# Supply_Fast_Servo.net
KiCad netlist of a schematic drawn in Altium Designer
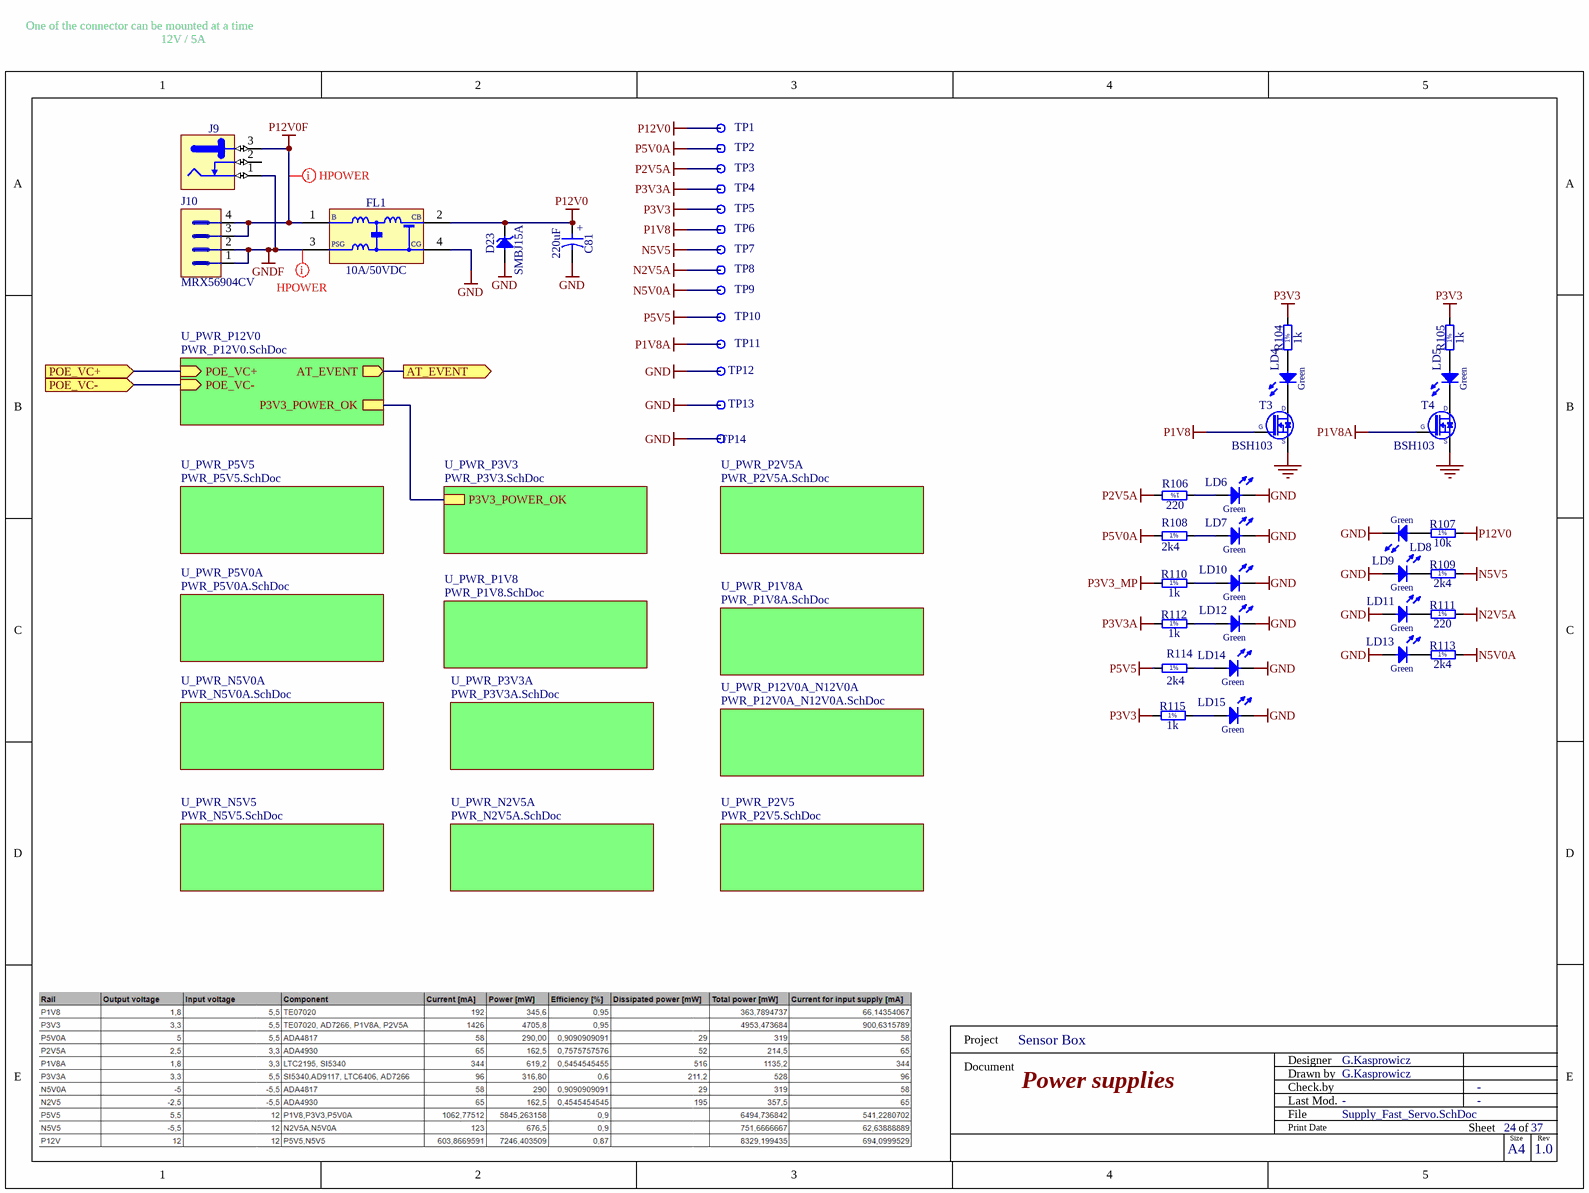
[diagram p0: Supply_Fast_Servo.SchDoc]

(export (version "E")
  (design (tool "Eeschema 10.0.6"))
  (components
    (comp (ref "C81")
      (value "220uF")
      (footprint "CAPAE830X620N")
      (description "Polarised capacitor")
      (fields
        (field (name "PART NUMBER") "CAE830-620_220UF_16V_20%")
        (field (name "VOLTAGE") "16V")
        (field (name "AUTHOR") "CERN DEM JLC")
      )
      (libsource (lib "Capacitors") (part "Capacitor - polarized"))
    )
    (comp (ref "D23")
      (value "SMBJ15A")
      (footprint "DIOM5336X265N")
      (description "Zener Diode")
      (fields
        (field (name "VOLTAGE") "15V")
        (field (name "POWER") "600W")
        (field (name "AUTHOR") "CERN DEM JLC")
      )
      (libsource (lib "ICs And Semiconductors") (part "Diode Zener"))
    )
    (comp (ref "FL1")
      (value "10A/50VDC")
      (footprint "FIL_MURATA_BNX02")
      (description "Block Type EMIFIL (LC Combined)")
      (fields
        (field (name "PART NUMBER") "FIL_MURATA_BNX022-01L")
        (field (name "MANUFACTURER") "MURATA")
        (field (name "AUTHOR") "CERN DEM JLC")
      )
      (libsource (lib "Inductors & Transformers") (part "FIL_MURATA_BNX02"))
    )
    (comp (ref "J9")
      (value "Jack")
      (footprint "SWITCHCRAFT_L712RA")
      (description "24V /3. 5A, 2.1mm Diameter Pin, SMD DC Power Supply Connector With  Break Contact")
      (fields
        (field (name "PART NUMBER") "SWITCHCRAFT_L712RA")
        (field (name "MANUFACTURER") "SWITCHCRAFT")
        (field (name "AUTHOR") "GK")
      )
      (libsource (lib "Stabilizer") (part "CON_DC_5A_THT_RA"))
    )
    (comp (ref "J10")
      (value "MRX56904CV")
      (footprint "MRX56904CV")
      (description "4.2mm cripm terminal header")
      (libsource (lib "Stabilizer") (part "CON_CRIMP_4.2mm_RA_4"))
    )
    (comp (ref "LD4")
      (value "Green")
      (footprint "LED_KINGBRIGHT_KPH-1608CGCK")
      (description "LED Green 1C 2A")
      (fields
        (field (name "MANUFACTURER PART NUMBER") "KPH-1608CGCK")
        (field (name "PART NUMBER") "LED_KINGBRIGHT_KPH-1608CGCK")
        (field (name "AUTHOR") "CERN DEM JLC")
      )
      (libsource (lib "ICs And Semiconductors") (part "LED Green 1C 2A"))
    )
    (comp (ref "LD5")
      (value "Green")
      (footprint "LED_KINGBRIGHT_KPH-1608CGCK")
      (description "LED Green 1C 2A")
      (fields
        (field (name "MANUFACTURER PART NUMBER") "KPH-1608CGCK")
        (field (name "PART NUMBER") "LED_KINGBRIGHT_KPH-1608CGCK")
        (field (name "AUTHOR") "CERN DEM JLC")
      )
      (libsource (lib "ICs And Semiconductors") (part "LED Green 1C 2A"))
    )
    (comp (ref "LD6")
      (value "Green")
      (footprint "LED_KINGBRIGHT_KPH-1608CGCK")
      (description "LED Green 1C 2A")
      (fields
        (field (name "PART NUMBER") "LED_KINGBRIGHT_KPH-1608CGCK")
        (field (name "MANUFACTURER") "KINGBRIGHT")
        (field (name "AUTHOR") "CERN DEM JLC")
      )
      (libsource (lib "ICs And Semiconductors") (part "LED Green 1C 2A"))
    )
    (comp (ref "LD7")
      (value "Green")
      (footprint "LED_KINGBRIGHT_KPH-1608CGCK")
      (description "LED Green 1C 2A")
      (fields
        (field (name "PART NUMBER") "LED_KINGBRIGHT_KPH-1608CGCK")
        (field (name "MANUFACTURER") "KINGBRIGHT")
        (field (name "AUTHOR") "CERN DEM JLC")
      )
      (libsource (lib "ICs And Semiconductors") (part "LED Green 1C 2A"))
    )
    (comp (ref "LD8")
      (value "Green")
      (footprint "LED_KINGBRIGHT_KPH-1608CGCK")
      (description "LED Green 1C 2A")
      (fields
        (field (name "PART NUMBER") "LED_KINGBRIGHT_KPH-1608CGCK")
        (field (name "MANUFACTURER") "KINGBRIGHT")
        (field (name "AUTHOR") "CERN DEM JLC")
      )
      (libsource (lib "ICs And Semiconductors") (part "LED Green 1C 2A"))
    )
    (comp (ref "LD9")
      (value "Green")
      (footprint "LED_KINGBRIGHT_KPH-1608CGCK")
      (description "LED Green 1C 2A")
      (fields
        (field (name "PART NUMBER") "LED_KINGBRIGHT_KPH-1608CGCK")
        (field (name "MANUFACTURER") "KINGBRIGHT")
        (field (name "AUTHOR") "CERN DEM JLC")
      )
      (libsource (lib "ICs And Semiconductors") (part "LED Green 1C 2A"))
    )
    (comp (ref "LD10")
      (value "Green")
      (footprint "LED_KINGBRIGHT_KPH-1608CGCK")
      (description "LED Green 1C 2A")
      (fields
        (field (name "PART NUMBER") "LED_KINGBRIGHT_KPH-1608CGCK")
        (field (name "MANUFACTURER") "KINGBRIGHT")
        (field (name "AUTHOR") "CERN DEM JLC")
      )
      (libsource (lib "ICs And Semiconductors") (part "LED Green 1C 2A"))
    )
    (comp (ref "LD11")
      (value "Green")
      (footprint "LED_KINGBRIGHT_KPH-1608CGCK")
      (description "LED Green 1C 2A")
      (fields
        (field (name "PART NUMBER") "LED_KINGBRIGHT_KPH-1608CGCK")
        (field (name "MANUFACTURER") "KINGBRIGHT")
        (field (name "AUTHOR") "CERN DEM JLC")
      )
      (libsource (lib "ICs And Semiconductors") (part "LED Green 1C 2A"))
    )
    (comp (ref "LD12")
      (value "Green")
      (footprint "LED_KINGBRIGHT_KPH-1608CGCK")
      (description "LED Green 1C 2A")
      (fields
        (field (name "PART NUMBER") "LED_KINGBRIGHT_KPH-1608CGCK")
        (field (name "MANUFACTURER") "KINGBRIGHT")
        (field (name "AUTHOR") "CERN DEM JLC")
      )
      (libsource (lib "ICs And Semiconductors") (part "LED Green 1C 2A"))
    )
    (comp (ref "LD13")
      (value "Green")
      (footprint "LED_KINGBRIGHT_KPH-1608CGCK")
      (description "LED Green 1C 2A")
      (fields
        (field (name "PART NUMBER") "LED_KINGBRIGHT_KPH-1608CGCK")
        (field (name "MANUFACTURER") "KINGBRIGHT")
        (field (name "AUTHOR") "CERN DEM JLC")
      )
      (libsource (lib "ICs And Semiconductors") (part "LED Green 1C 2A"))
    )
    (comp (ref "LD14")
      (value "Green")
      (footprint "LED_KINGBRIGHT_KPH-1608CGCK")
      (description "LED Green 1C 2A")
      (fields
        (field (name "PART NUMBER") "LED_KINGBRIGHT_KPH-1608CGCK")
        (field (name "MANUFACTURER") "KINGBRIGHT")
        (field (name "AUTHOR") "CERN DEM JLC")
      )
      (libsource (lib "ICs And Semiconductors") (part "LED Green 1C 2A"))
    )
    (comp (ref "LD15")
      (value "Green")
      (footprint "LED_KINGBRIGHT_KPH-1608CGCK")
      (description "LED Green 1C 2A")
      (fields
        (field (name "PART NUMBER") "LED_KINGBRIGHT_KPH-1608CGCK")
        (field (name "MANUFACTURER") "KINGBRIGHT")
        (field (name "AUTHOR") "CERN DEM JLC")
      )
      (libsource (lib "ICs And Semiconductors") (part "LED Green 1C 2A"))
    )
    (comp (ref "R104")
      (value "1k")
      (footprint "RESC1005X40N")
      (description "Resistor - 1%")
      (fields
        (field (name "PART NUMBER") "R0402_1K_1%_0.0625W_100PPM")
        (field (name "POWER") "0.0625W")
        (field (name "AUTHOR") "CERN DEM JLC")
      )
      (libsource (lib "Resistors") (part "Resistor - 1%"))
    )
    (comp (ref "R105")
      (value "1k")
      (footprint "RESC1005X40N")
      (description "Resistor - 1%")
      (fields
        (field (name "PART NUMBER") "R0402_1K_1%_0.0625W_100PPM")
        (field (name "POWER") "0.0625W")
        (field (name "AUTHOR") "CERN DEM JLC")
      )
      (libsource (lib "Resistors") (part "Resistor - 1%"))
    )
    (comp (ref "R106")
      (value "220")
      (footprint "RESC1608X55N")
      (description "Resistor - 1%")
      (fields
        (field (name "PART NUMBER") "R0603_220R_1%_0.1W_100PPM")
        (field (name "POWER") "0.1W")
        (field (name "AUTHOR") "CERN DEM JLC")
      )
      (libsource (lib "Resistors") (part "Resistor - 1%"))
    )
    (comp (ref "R107")
      (value "10k")
      (footprint "RESC1005X40N")
      (description "Resistor - 1%")
      (fields
        (field (name "PART NUMBER") "R0402_10K_1%_0.0625W_100PPM")
        (field (name "POWER") "0.0625W")
        (field (name "AUTHOR") "CERN DEM JLC")
      )
      (libsource (lib "Resistors") (part "Resistor - 1%"))
    )
    (comp (ref "R108")
      (value "2k4")
      (footprint "RESC1005X40N")
      (description "Resistor - 1%")
      (fields
        (field (name "PART NUMBER") "R0402_2K4_1%_0.0625W_100PPM")
        (field (name "POWER") "0.0625W")
        (field (name "AUTHOR") "CERN DEM JLC")
      )
      (libsource (lib "Resistors") (part "Resistor - 1%"))
    )
    (comp (ref "R109")
      (value "2k4")
      (footprint "RESC1005X40N")
      (description "Resistor - 1%")
      (fields
        (field (name "PART NUMBER") "R0402_2K4_1%_0.0625W_100PPM")
        (field (name "POWER") "0.0625W")
        (field (name "AUTHOR") "CERN DEM JLC")
      )
      (libsource (lib "Resistors") (part "Resistor - 1%"))
    )
    (comp (ref "R110")
      (value "1k")
      (footprint "RESC1005X40N")
      (description "Resistor - 1%")
      (fields
        (field (name "PART NUMBER") "R0402_1K_1%_0.0625W_100PPM")
        (field (name "POWER") "0.0625W")
        (field (name "AUTHOR") "CERN DEM JLC")
      )
      (libsource (lib "Resistors") (part "Resistor - 1%"))
    )
    (comp (ref "R111")
      (value "220")
      (footprint "RESC1608X55N")
      (description "Resistor - 1%")
      (fields
        (field (name "PART NUMBER") "R0603_220R_1%_0.1W_100PPM")
        (field (name "POWER") "0.1W")
        (field (name "AUTHOR") "CERN DEM JLC")
      )
      (libsource (lib "Resistors") (part "Resistor - 1%"))
    )
    (comp (ref "R112")
      (value "1k")
      (footprint "RESC1005X40N")
      (description "Resistor - 1%")
      (fields
        (field (name "PART NUMBER") "R0402_1K_1%_0.0625W_100PPM")
        (field (name "POWER") "0.0625W")
        (field (name "AUTHOR") "CERN DEM JLC")
      )
      (libsource (lib "Resistors") (part "Resistor - 1%"))
    )
    (comp (ref "R113")
      (value "2k4")
      (footprint "RESC1005X40N")
      (description "Resistor - 1%")
      (fields
        (field (name "PART NUMBER") "R0402_2K4_1%_0.0625W_100PPM")
        (field (name "POWER") "0.0625W")
        (field (name "AUTHOR") "CERN DEM JLC")
      )
      (libsource (lib "Resistors") (part "Resistor - 1%"))
    )
    (comp (ref "R114")
      (value "2k4")
      (footprint "RESC1005X40N")
      (description "Resistor - 1%")
      (fields
        (field (name "PART NUMBER") "R0402_2K4_1%_0.0625W_100PPM")
        (field (name "POWER") "0.0625W")
        (field (name "AUTHOR") "CERN DEM JLC")
      )
      (libsource (lib "Resistors") (part "Resistor - 1%"))
    )
    (comp (ref "R115")
      (value "1k")
      (footprint "RESC1005X40N")
      (description "Resistor - 1%")
      (fields
        (field (name "PART NUMBER") "R0402_1K_1%_0.0625W_100PPM")
        (field (name "POWER") "0.0625W")
        (field (name "AUTHOR") "CERN DEM JLC")
      )
      (libsource (lib "Resistors") (part "Resistor - 1%"))
    )
    (comp (ref "T3")
      (value "BSH103")
      (footprint "SOT95P230X110-3N")
      (description "N-CHANNEL MOSFET WITH DIODE")
      (fields (field (name "MANUFACTURER") "NEXPERIA") (field (name "AUTHOR") "CERN DEM JLC"))
      (libsource (lib "ICs And Semiconductors") (part "N-MOSFET-D 1G 2S 3D"))
    )
    (comp (ref "T4")
      (value "BSH103")
      (footprint "SOT95P230X110-3N")
      (description "N-CHANNEL MOSFET WITH DIODE")
      (fields (field (name "MANUFACTURER") "NEXPERIA") (field (name "AUTHOR") "CERN DEM JLC"))
      (libsource (lib "ICs And Semiconductors") (part "N-MOSFET-D 1G 2S 3D"))
    )
    (comp (ref "TP1")
      (value "Test Point")
      (footprint "TPS127")
      (fields (field (name "PART NUMBER") "SMD_PAD_1.27X1.27MM") (field (name "AUTHOR") "CERN DEM JLC"))
      (libsource (lib "Eletro-mechanical") (part "Test Point"))
    )
    (comp (ref "TP2")
      (value "Test Point")
      (footprint "TPS127")
      (fields (field (name "PART NUMBER") "SMD_PAD_1.27X1.27MM") (field (name "AUTHOR") "CERN DEM JLC"))
      (libsource (lib "Eletro-mechanical") (part "Test Point"))
    )
    (comp (ref "TP3")
      (value "Test Point")
      (footprint "TPS127")
      (fields (field (name "PART NUMBER") "SMD_PAD_1.27X1.27MM") (field (name "AUTHOR") "CERN DEM JLC"))
      (libsource (lib "Eletro-mechanical") (part "Test Point"))
    )
    (comp (ref "TP4")
      (value "Test Point")
      (footprint "TPS127")
      (fields (field (name "PART NUMBER") "SMD_PAD_1.27X1.27MM") (field (name "AUTHOR") "CERN DEM JLC"))
      (libsource (lib "Eletro-mechanical") (part "Test Point"))
    )
    (comp (ref "TP5")
      (value "Test Point")
      (footprint "TPS127")
      (fields (field (name "PART NUMBER") "SMD_PAD_1.27X1.27MM") (field (name "AUTHOR") "CERN DEM JLC"))
      (libsource (lib "Eletro-mechanical") (part "Test Point"))
    )
    (comp (ref "TP6")
      (value "Test Point")
      (footprint "TPS127")
      (fields (field (name "PART NUMBER") "SMD_PAD_1.27X1.27MM") (field (name "AUTHOR") "CERN DEM JLC"))
      (libsource (lib "Eletro-mechanical") (part "Test Point"))
    )
    (comp (ref "TP7")
      (value "Test Point")
      (footprint "TPS127")
      (fields (field (name "PART NUMBER") "SMD_PAD_1.27X1.27MM") (field (name "AUTHOR") "CERN DEM JLC"))
      (libsource (lib "Eletro-mechanical") (part "Test Point"))
    )
    (comp (ref "TP8")
      (value "Test Point")
      (footprint "TPS127")
      (fields (field (name "PART NUMBER") "SMD_PAD_1.27X1.27MM") (field (name "AUTHOR") "CERN DEM JLC"))
      (libsource (lib "Eletro-mechanical") (part "Test Point"))
    )
    (comp (ref "TP9")
      (value "Test Point")
      (footprint "TPS127")
      (fields (field (name "PART NUMBER") "SMD_PAD_1.27X1.27MM") (field (name "AUTHOR") "CERN DEM JLC"))
      (libsource (lib "Eletro-mechanical") (part "Test Point"))
    )
    (comp (ref "TP10")
      (value "Test Point")
      (footprint "TPS127")
      (fields (field (name "PART NUMBER") "SMD_PAD_1.27X1.27MM") (field (name "AUTHOR") "CERN DEM JLC"))
      (libsource (lib "Eletro-mechanical") (part "Test Point"))
    )
    (comp (ref "TP11")
      (value "Test Point")
      (footprint "TPS127")
      (fields (field (name "PART NUMBER") "SMD_PAD_1.27X1.27MM") (field (name "AUTHOR") "CERN DEM JLC"))
      (libsource (lib "Eletro-mechanical") (part "Test Point"))
    )
    (comp (ref "TP12")
      (value "Test Point")
      (footprint "TPS127")
      (fields (field (name "PART NUMBER") "SMD_PAD_1.27X1.27MM") (field (name "AUTHOR") "CERN DEM JLC"))
      (libsource (lib "Eletro-mechanical") (part "Test Point"))
    )
    (comp (ref "TP13")
      (value "Test Point")
      (footprint "TPS127")
      (fields (field (name "PART NUMBER") "SMD_PAD_1.27X1.27MM") (field (name "AUTHOR") "CERN DEM JLC"))
      (libsource (lib "Eletro-mechanical") (part "Test Point"))
    )
    (comp (ref "TP14")
      (value "Plated Hole")
      (footprint "c150h100")
      (description "Single Terminal Socket")
      (fields (field (name "PART NUMBER") "PLATED_HOLE1.0_PAD1.5") (field (name "AUTHOR") "CERN DEM JLC"))
      (libsource (lib "Eletro-mechanical") (part "Single Terminal Socket"))
    )
  )
  (nets
    (net (code "5") (name "GND") (class "Default")
      (node (ref "C81") (pin "2") (pinfunction "2_2") (pintype "passive"))
      (node (ref "D23") (pin "2") (pinfunction "A_2") (pintype "passive"))
      (node (ref "FL1") (pin "4") (pinfunction "CG_4") (pintype "passive"))
      (node (ref "LD10") (pin "1") (pinfunction "C_1") (pintype "passive"))
      (node (ref "LD11") (pin "2") (pinfunction "A_2") (pintype "passive"))
      (node (ref "LD12") (pin "1") (pinfunction "C_1") (pintype "passive"))
      (node (ref "LD13") (pin "2") (pinfunction "A_2") (pintype "passive"))
      (node (ref "LD14") (pin "1") (pinfunction "C_1") (pintype "passive"))
      (node (ref "LD15") (pin "1") (pinfunction "C_1") (pintype "passive"))
      (node (ref "LD6") (pin "1") (pinfunction "C_1") (pintype "passive"))
      (node (ref "LD7") (pin "1") (pinfunction "C_1") (pintype "passive"))
      (node (ref "LD8") (pin "1") (pinfunction "C_1") (pintype "passive"))
      (node (ref "LD9") (pin "2") (pinfunction "A_2") (pintype "passive"))
      (node (ref "T3") (pin "2") (pinfunction "S_2") (pintype "passive"))
      (node (ref "T4") (pin "2") (pinfunction "S_2") (pintype "passive"))
      (node (ref "TP12") (pin "1") (pinfunction "1_1") (pintype "bidirectional"))
      (node (ref "TP13") (pin "1") (pinfunction "1_1") (pintype "bidirectional"))
      (node (ref "TP14") (pin "1") (pinfunction "1_1") (pintype "bidirectional"))
    )
    (net (code "6") (name "GNDF") (class "Default")
      (node (ref "FL1") (pin "3") (pinfunction "PSG_3") (pintype "passive"))
      (node (ref "J10") (pin "1") (pinfunction "1_1") (pintype "bidirectional"))
      (node (ref "J10") (pin "2") (pinfunction "2_2") (pintype "bidirectional"))
      (node (ref "J9") (pin "1") (pinfunction "1_1") (pintype "bidirectional"))
    )
    (net (code "7") (name "N2V5A") (class "Default")
      (node (ref "R111") (pin "2") (pinfunction "2_2") (pintype "passive"))
      (node (ref "TP8") (pin "1") (pinfunction "1_1") (pintype "bidirectional"))
    )
    (net (code "8") (name "N5V0A") (class "Default")
      (node (ref "R113") (pin "2") (pinfunction "2_2") (pintype "passive"))
      (node (ref "TP9") (pin "1") (pinfunction "1_1") (pintype "bidirectional"))
    )
    (net (code "9") (name "N5V5") (class "Default")
      (node (ref "R109") (pin "2") (pinfunction "2_2") (pintype "passive"))
      (node (ref "TP7") (pin "1") (pinfunction "1_1") (pintype "bidirectional"))
    )
    (net (code "10") (name "Net-(LD4-A)") (class "Default")
      (node (ref "LD4") (pin "2") (pinfunction "A_2") (pintype "passive"))
      (node (ref "R104") (pin "1") (pinfunction "1_1") (pintype "passive"))
    )
    (net (code "11") (name "Net-(LD4-C)") (class "Default")
      (node (ref "LD4") (pin "1") (pinfunction "C_1") (pintype "passive"))
      (node (ref "T3") (pin "3") (pinfunction "D_3") (pintype "passive"))
    )
    (net (code "12") (name "Net-(LD5-A)") (class "Default")
      (node (ref "LD5") (pin "2") (pinfunction "A_2") (pintype "passive"))
      (node (ref "R105") (pin "1") (pinfunction "1_1") (pintype "passive"))
    )
    (net (code "13") (name "Net-(LD5-C)") (class "Default")
      (node (ref "LD5") (pin "1") (pinfunction "C_1") (pintype "passive"))
      (node (ref "T4") (pin "3") (pinfunction "D_3") (pintype "passive"))
    )
    (net (code "14") (name "Net-(LD6-A)") (class "Default")
      (node (ref "LD6") (pin "2") (pinfunction "A_2") (pintype "passive"))
      (node (ref "R106") (pin "1") (pinfunction "1_1") (pintype "passive"))
    )
    (net (code "15") (name "Net-(LD7-A)") (class "Default")
      (node (ref "LD7") (pin "2") (pinfunction "A_2") (pintype "passive"))
      (node (ref "R108") (pin "2") (pinfunction "2_2") (pintype "passive"))
    )
    (net (code "16") (name "Net-(LD8-A)") (class "Default")
      (node (ref "LD8") (pin "2") (pinfunction "A_2") (pintype "passive"))
      (node (ref "R107") (pin "1") (pinfunction "1_1") (pintype "passive"))
    )
    (net (code "17") (name "Net-(LD9-C)") (class "Default")
      (node (ref "LD9") (pin "1") (pinfunction "C_1") (pintype "passive"))
      (node (ref "R109") (pin "1") (pinfunction "1_1") (pintype "passive"))
    )
    (net (code "18") (name "Net-(LD10-A)") (class "Default")
      (node (ref "LD10") (pin "2") (pinfunction "A_2") (pintype "passive"))
      (node (ref "R110") (pin "2") (pinfunction "2_2") (pintype "passive"))
    )
    (net (code "19") (name "Net-(LD11-C)") (class "Default")
      (node (ref "LD11") (pin "1") (pinfunction "C_1") (pintype "passive"))
      (node (ref "R111") (pin "1") (pinfunction "1_1") (pintype "passive"))
    )
    (net (code "20") (name "Net-(LD12-A)") (class "Default")
      (node (ref "LD12") (pin "2") (pinfunction "A_2") (pintype "passive"))
      (node (ref "R112") (pin "2") (pinfunction "2_2") (pintype "passive"))
    )
    (net (code "21") (name "Net-(LD13-C)") (class "Default")
      (node (ref "LD13") (pin "1") (pinfunction "C_1") (pintype "passive"))
      (node (ref "R113") (pin "1") (pinfunction "1_1") (pintype "passive"))
    )
    (net (code "22") (name "Net-(LD14-A)") (class "Default")
      (node (ref "LD14") (pin "2") (pinfunction "A_2") (pintype "passive"))
      (node (ref "R114") (pin "2") (pinfunction "2_2") (pintype "passive"))
    )
    (net (code "23") (name "Net-(LD15-A)") (class "Default")
      (node (ref "LD15") (pin "2") (pinfunction "A_2") (pintype "passive"))
      (node (ref "R115") (pin "2") (pinfunction "2_2") (pintype "passive"))
    )
    (net (code "24") (name "P1V8") (class "Default")
      (node (ref "T3") (pin "1") (pinfunction "G_1") (pintype "passive"))
      (node (ref "TP6") (pin "1") (pinfunction "1_1") (pintype "bidirectional"))
    )
    (net (code "25") (name "P1V8A") (class "Default")
      (node (ref "T4") (pin "1") (pinfunction "G_1") (pintype "passive"))
      (node (ref "TP11") (pin "1") (pinfunction "1_1") (pintype "bidirectional"))
    )
    (net (code "26") (name "P2V5A") (class "Default")
      (node (ref "R106") (pin "2") (pinfunction "2_2") (pintype "passive"))
      (node (ref "TP3") (pin "1") (pinfunction "1_1") (pintype "bidirectional"))
    )
    (net (code "27") (name "P3V3") (class "Default")
      (node (ref "R104") (pin "2") (pinfunction "2_2") (pintype "passive"))
      (node (ref "R105") (pin "2") (pinfunction "2_2") (pintype "passive"))
      (node (ref "R115") (pin "1") (pinfunction "1_1") (pintype "passive"))
      (node (ref "TP5") (pin "1") (pinfunction "1_1") (pintype "bidirectional"))
    )
    (net (code "28") (name "P3V3A") (class "Default")
      (node (ref "R112") (pin "1") (pinfunction "1_1") (pintype "passive"))
      (node (ref "TP4") (pin "1") (pinfunction "1_1") (pintype "bidirectional"))
    )
    (net (code "29") (name "P3V3_MP") (class "Default")
      (node (ref "R110") (pin "1") (pinfunction "1_1") (pintype "passive"))
    )
    (net (code "30") (name "P5V0A") (class "Default")
      (node (ref "R108") (pin "1") (pinfunction "1_1") (pintype "passive"))
      (node (ref "TP2") (pin "1") (pinfunction "1_1") (pintype "bidirectional"))
    )
    (net (code "31") (name "P5V5") (class "Default")
      (node (ref "R114") (pin "1") (pinfunction "1_1") (pintype "passive"))
      (node (ref "TP10") (pin "1") (pinfunction "1_1") (pintype "bidirectional"))
    )
    (net (code "32") (name "P12V0") (class "Default")
      (node (ref "C81") (pin "1") (pinfunction "1_1") (pintype "passive"))
      (node (ref "D23") (pin "1") (pinfunction "C_1") (pintype "passive"))
      (node (ref "FL1") (pin "2") (pinfunction "CB_2") (pintype "passive"))
      (node (ref "R107") (pin "2") (pinfunction "2_2") (pintype "passive"))
      (node (ref "TP1") (pin "1") (pinfunction "1_1") (pintype "bidirectional"))
    )
    (net (code "33") (name "P12V0F") (class "Default")
      (node (ref "FL1") (pin "1") (pinfunction "B_1") (pintype "passive"))
      (node (ref "J10") (pin "3") (pinfunction "3_3") (pintype "bidirectional"))
      (node (ref "J10") (pin "4") (pinfunction "4_4") (pintype "bidirectional"))
      (node (ref "J9") (pin "3") (pinfunction "3_3") (pintype "bidirectional"))
    )
    (net (code "34") (name "unconnected-(J9-Pad2)") (class "Default")
      (node (ref "J9") (pin "2") (pinfunction "2_2") (pintype "bidirectional"))
    )
  )
)
